# top_schem_rev10_2.net
KiCad netlist of a schematic drawn in Altium Designer
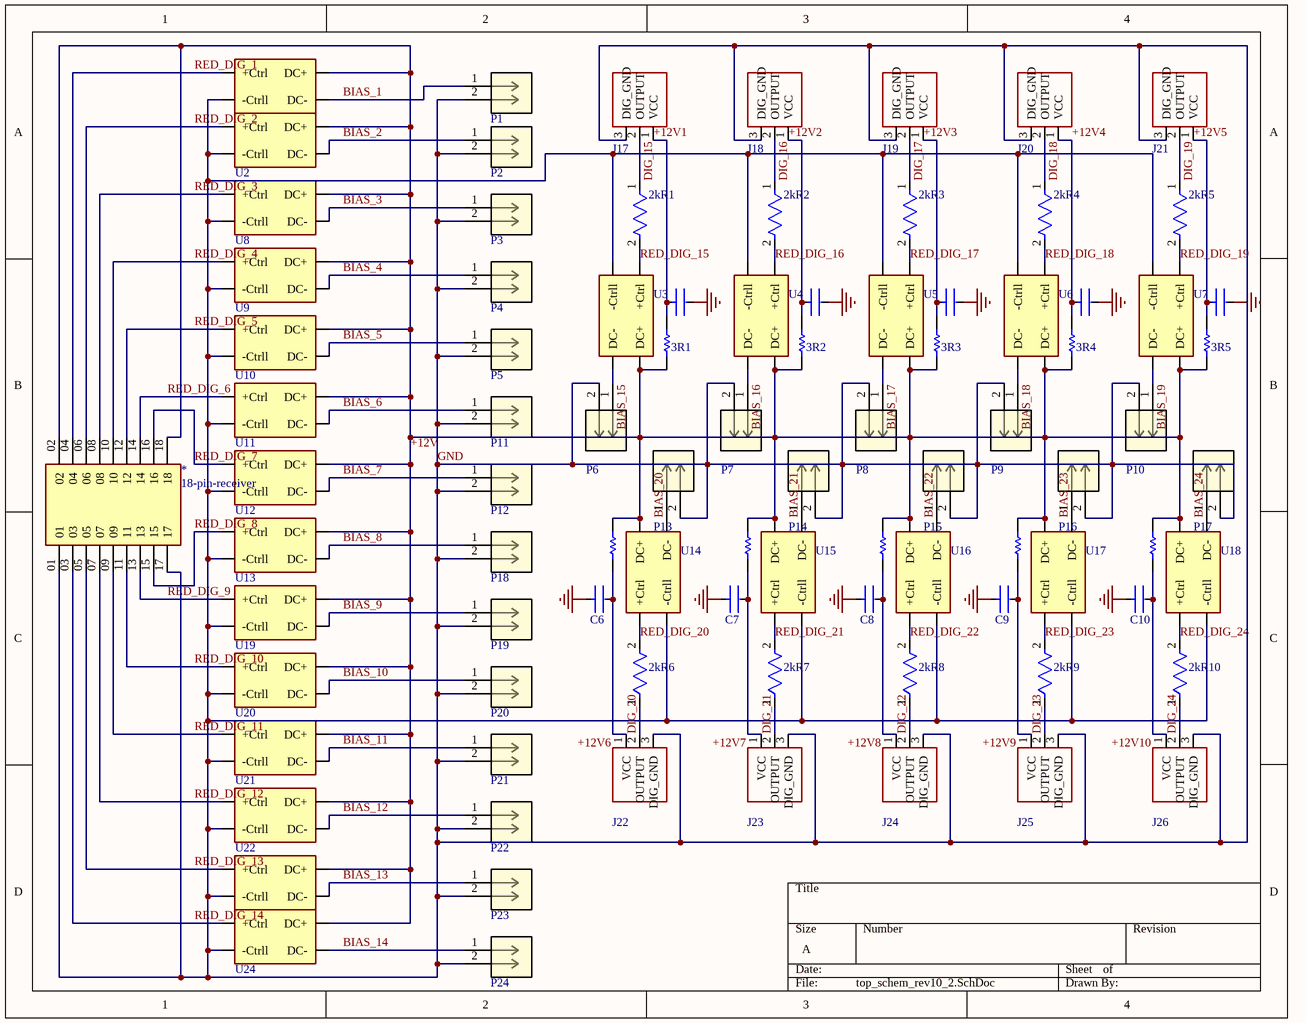
[diagram p0: top_schem_rev10_2.SchDoc]

(export (version "E")
  (design (tool "Eeschema 10.0.6"))
  (components
    (comp (ref "*")
      (value "18-pin-receiver")
      (footprint "18-pin-receiver")
      (libsource (lib "top_schlib") (part "18-pin-receiver"))
    )
    (comp (ref "2kR1")
      (value "CRCW06031K80FKEA")
      (footprint "2kOhm")
      (description "Res Thick Film 0603 1.8K Ohm 1% 1/10W ±100ppm/°C Molded SMD Paper T/R")
      (fields (field (name "MANUFACTURER") "Vishay") (field (name "TOLERANCE") "1%"))
      (libsource (lib "ps_schlib") (part "CRCW06031K80FKEA"))
    )
    (comp (ref "2kR2")
      (value "CRCW06031K80FKEA")
      (footprint "2kOhm")
      (description "Res Thick Film 0603 1.8K Ohm 1% 1/10W ±100ppm/°C Molded SMD Paper T/R")
      (fields (field (name "MANUFACTURER") "Vishay") (field (name "TOLERANCE") "1%"))
      (libsource (lib "ps_schlib") (part "CRCW06031K80FKEA"))
    )
    (comp (ref "2kR3")
      (value "CRCW06031K80FKEA")
      (footprint "2kOhm")
      (description "Res Thick Film 0603 1.8K Ohm 1% 1/10W ±100ppm/°C Molded SMD Paper T/R")
      (fields (field (name "MANUFACTURER") "Vishay") (field (name "TOLERANCE") "1%"))
      (libsource (lib "ps_schlib") (part "CRCW06031K80FKEA"))
    )
    (comp (ref "2kR4")
      (value "CRCW06031K80FKEA")
      (footprint "2kOhm")
      (description "Res Thick Film 0603 1.8K Ohm 1% 1/10W ±100ppm/°C Molded SMD Paper T/R")
      (fields (field (name "MANUFACTURER") "Vishay") (field (name "TOLERANCE") "1%"))
      (libsource (lib "ps_schlib") (part "CRCW06031K80FKEA"))
    )
    (comp (ref "2kR5")
      (value "CRCW06031K80FKEA")
      (footprint "2kOhm")
      (description "Res Thick Film 0603 1.8K Ohm 1% 1/10W ±100ppm/°C Molded SMD Paper T/R")
      (fields (field (name "MANUFACTURER") "Vishay") (field (name "TOLERANCE") "1%"))
      (libsource (lib "ps_schlib") (part "CRCW06031K80FKEA"))
    )
    (comp (ref "2kR6")
      (value "CRCW06031K80FKEA")
      (footprint "2kOhm")
      (description "Res Thick Film 0603 1.8K Ohm 1% 1/10W ±100ppm/°C Molded SMD Paper T/R")
      (fields (field (name "MANUFACTURER") "Vishay") (field (name "TOLERANCE") "1%"))
      (libsource (lib "ps_schlib") (part "CRCW06031K80FKEA"))
    )
    (comp (ref "2kR7")
      (value "CRCW06031K80FKEA")
      (footprint "2kOhm")
      (description "Res Thick Film 0603 1.8K Ohm 1% 1/10W ±100ppm/°C Molded SMD Paper T/R")
      (fields (field (name "MANUFACTURER") "Vishay") (field (name "TOLERANCE") "1%"))
      (libsource (lib "ps_schlib") (part "CRCW06031K80FKEA"))
    )
    (comp (ref "2kR8")
      (value "CRCW06031K80FKEA")
      (footprint "2kOhm")
      (description "Res Thick Film 0603 1.8K Ohm 1% 1/10W ±100ppm/°C Molded SMD Paper T/R")
      (fields (field (name "MANUFACTURER") "Vishay") (field (name "TOLERANCE") "1%"))
      (libsource (lib "ps_schlib") (part "CRCW06031K80FKEA"))
    )
    (comp (ref "2kR9")
      (value "CRCW06031K80FKEA")
      (footprint "2kOhm")
      (description "Res Thick Film 0603 1.8K Ohm 1% 1/10W ±100ppm/°C Molded SMD Paper T/R")
      (fields (field (name "MANUFACTURER") "Vishay") (field (name "TOLERANCE") "1%"))
      (libsource (lib "ps_schlib") (part "CRCW06031K80FKEA"))
    )
    (comp (ref "2kR10")
      (value "CRCW06031K80FKEA")
      (footprint "2kOhm")
      (description "Res Thick Film 0603 1.8K Ohm 1% 1/10W ±100ppm/°C Molded SMD Paper T/R")
      (fields (field (name "MANUFACTURER") "Vishay") (field (name "TOLERANCE") "1%"))
      (libsource (lib "ps_schlib") (part "CRCW06031K80FKEA"))
    )
    (comp (ref "3R1")
      (value "ERJ-2BQJR30X")
      (footprint "03 Ohm")
      (description "RES 0.3 OHM 5% 1/6W 0402")
      (fields (field (name "MANUFACTURER") "Panasonic") (field (name "TOLERANCE") "5%"))
      (libsource (lib "ps_schlib") (part "ERJ-2BQJR30X"))
    )
    (comp (ref "3R2")
      (value "ERJ-2BQJR30X")
      (footprint "03 Ohm")
      (description "RES 0.3 OHM 5% 1/6W 0402")
      (fields (field (name "MANUFACTURER") "Panasonic") (field (name "TOLERANCE") "5%"))
      (libsource (lib "ps_schlib") (part "ERJ-2BQJR30X"))
    )
    (comp (ref "3R3")
      (value "ERJ-2BQJR30X")
      (footprint "03 Ohm")
      (description "RES 0.3 OHM 5% 1/6W 0402")
      (fields (field (name "MANUFACTURER") "Panasonic") (field (name "TOLERANCE") "5%"))
      (libsource (lib "ps_schlib") (part "ERJ-2BQJR30X"))
    )
    (comp (ref "3R4")
      (value "ERJ-2BQJR30X")
      (footprint "03 Ohm")
      (description "RES 0.3 OHM 5% 1/6W 0402")
      (fields (field (name "MANUFACTURER") "Panasonic") (field (name "TOLERANCE") "5%"))
      (libsource (lib "ps_schlib") (part "ERJ-2BQJR30X"))
    )
    (comp (ref "3R5")
      (value "ERJ-2BQJR30X")
      (footprint "03 Ohm")
      (description "RES 0.3 OHM 5% 1/6W 0402")
      (fields (field (name "MANUFACTURER") "Panasonic") (field (name "TOLERANCE") "5%"))
      (libsource (lib "ps_schlib") (part "ERJ-2BQJR30X"))
    )
    (comp (ref "3R6")
      (value "ERJ-2BQJR30X")
      (footprint "03 Ohm")
      (description "RES 0.3 OHM 5% 1/6W 0402")
      (fields (field (name "MANUFACTURER") "Panasonic") (field (name "TOLERANCE") "5%"))
      (libsource (lib "ps_schlib") (part "ERJ-2BQJR30X"))
    )
    (comp (ref "3R7")
      (value "ERJ-2BQJR30X")
      (footprint "03 Ohm")
      (description "RES 0.3 OHM 5% 1/6W 0402")
      (fields (field (name "MANUFACTURER") "Panasonic") (field (name "TOLERANCE") "5%"))
      (libsource (lib "ps_schlib") (part "ERJ-2BQJR30X"))
    )
    (comp (ref "3R8")
      (value "ERJ-2BQJR30X")
      (footprint "03 Ohm")
      (description "RES 0.3 OHM 5% 1/6W 0402")
      (fields (field (name "MANUFACTURER") "Panasonic") (field (name "TOLERANCE") "5%"))
      (libsource (lib "ps_schlib") (part "ERJ-2BQJR30X"))
    )
    (comp (ref "3R9")
      (value "ERJ-2BQJR30X")
      (footprint "03 Ohm")
      (description "RES 0.3 OHM 5% 1/6W 0402")
      (fields (field (name "MANUFACTURER") "Panasonic") (field (name "TOLERANCE") "5%"))
      (libsource (lib "ps_schlib") (part "ERJ-2BQJR30X"))
    )
    (comp (ref "3R10")
      (value "ERJ-2BQJR30X")
      (footprint "03 Ohm")
      (description "RES 0.3 OHM 5% 1/6W 0402")
      (fields (field (name "MANUFACTURER") "Panasonic") (field (name "TOLERANCE") "5%"))
      (libsource (lib "ps_schlib") (part "ERJ-2BQJR30X"))
    )
    (comp (ref "C1")
      (value "C0805C104K5RACTU")
      (footprint "100nF")
      (description "Cap Ceramic 0.1uF 50V X7R 10% SMD 2.0 x 1.2 mm 125 C Paper T/R")
      (fields (field (name "MANUFACTURER") "KEMET") (field (name "TOLERANCE") "10%"))
      (libsource (lib "ps_schlib") (part "C0805C104K5RACTU"))
    )
    (comp (ref "C2")
      (value "C0805C104K5RACTU")
      (footprint "100nF")
      (description "Cap Ceramic 0.1uF 50V X7R 10% SMD 2.0 x 1.2 mm 125 C Paper T/R")
      (fields (field (name "MANUFACTURER") "KEMET") (field (name "TOLERANCE") "10%"))
      (libsource (lib "ps_schlib") (part "C0805C104K5RACTU"))
    )
    (comp (ref "C3")
      (value "C0805C104K5RACTU")
      (footprint "100nF")
      (description "Cap Ceramic 0.1uF 50V X7R 10% SMD 2.0 x 1.2 mm 125 C Paper T/R")
      (fields (field (name "MANUFACTURER") "KEMET") (field (name "TOLERANCE") "10%"))
      (libsource (lib "ps_schlib") (part "C0805C104K5RACTU"))
    )
    (comp (ref "C4")
      (value "C0805C104K5RACTU")
      (footprint "100nF")
      (description "Cap Ceramic 0.1uF 50V X7R 10% SMD 2.0 x 1.2 mm 125 C Paper T/R")
      (fields (field (name "MANUFACTURER") "KEMET") (field (name "TOLERANCE") "10%"))
      (libsource (lib "ps_schlib") (part "C0805C104K5RACTU"))
    )
    (comp (ref "C5")
      (value "C0805C104K5RACTU")
      (footprint "100nF")
      (description "Cap Ceramic 0.1uF 50V X7R 10% SMD 2.0 x 1.2 mm 125 C Paper T/R")
      (fields (field (name "MANUFACTURER") "KEMET") (field (name "TOLERANCE") "10%"))
      (libsource (lib "ps_schlib") (part "C0805C104K5RACTU"))
    )
    (comp (ref "C6")
      (value "C0805C104K5RACTU")
      (footprint "100nF")
      (description "Cap Ceramic 0.1uF 50V X7R 10% SMD 2.0 x 1.2 mm 125 C Paper T/R")
      (fields (field (name "MANUFACTURER") "KEMET") (field (name "TOLERANCE") "10%"))
      (libsource (lib "ps_schlib") (part "C0805C104K5RACTU"))
    )
    (comp (ref "C7")
      (value "C0805C104K5RACTU")
      (footprint "100nF")
      (description "Cap Ceramic 0.1uF 50V X7R 10% SMD 2.0 x 1.2 mm 125 C Paper T/R")
      (fields (field (name "MANUFACTURER") "KEMET") (field (name "TOLERANCE") "10%"))
      (libsource (lib "ps_schlib") (part "C0805C104K5RACTU"))
    )
    (comp (ref "C8")
      (value "C0805C104K5RACTU")
      (footprint "100nF")
      (description "Cap Ceramic 0.1uF 50V X7R 10% SMD 2.0 x 1.2 mm 125 C Paper T/R")
      (fields (field (name "MANUFACTURER") "KEMET") (field (name "TOLERANCE") "10%"))
      (libsource (lib "ps_schlib") (part "C0805C104K5RACTU"))
    )
    (comp (ref "C9")
      (value "C0805C104K5RACTU")
      (footprint "100nF")
      (description "Cap Ceramic 0.1uF 50V X7R 10% SMD 2.0 x 1.2 mm 125 C Paper T/R")
      (fields (field (name "MANUFACTURER") "KEMET") (field (name "TOLERANCE") "10%"))
      (libsource (lib "ps_schlib") (part "C0805C104K5RACTU"))
    )
    (comp (ref "C10")
      (value "C0805C104K5RACTU")
      (footprint "100nF")
      (description "Cap Ceramic 0.1uF 50V X7R 10% SMD 2.0 x 1.2 mm 125 C Paper T/R")
      (fields (field (name "MANUFACTURER") "KEMET") (field (name "TOLERANCE") "10%"))
      (libsource (lib "ps_schlib") (part "C0805C104K5RACTU"))
    )
    (comp (ref "J17")
      (value "IF-D95T")
      (footprint "IF-D95")
      (description "DETECTOR PHOTOLOGIC TTL/CMOS")
      (fields (field (name "MANUFACTURER") "Industrial Fiber Optics"))
      (libsource (lib "ps_schlib") (part "IF-D95T"))
    )
    (comp (ref "J18")
      (value "IF-D95T")
      (footprint "IF-D95")
      (description "DETECTOR PHOTOLOGIC TTL/CMOS")
      (fields (field (name "MANUFACTURER") "Industrial Fiber Optics"))
      (libsource (lib "ps_schlib") (part "IF-D95T"))
    )
    (comp (ref "J19")
      (value "IF-D95T")
      (footprint "IF-D95")
      (description "DETECTOR PHOTOLOGIC TTL/CMOS")
      (fields (field (name "MANUFACTURER") "Industrial Fiber Optics"))
      (libsource (lib "ps_schlib") (part "IF-D95T"))
    )
    (comp (ref "J20")
      (value "IF-D95T")
      (footprint "IF-D95")
      (description "DETECTOR PHOTOLOGIC TTL/CMOS")
      (fields (field (name "MANUFACTURER") "Industrial Fiber Optics"))
      (libsource (lib "ps_schlib") (part "IF-D95T"))
    )
    (comp (ref "J21")
      (value "IF-D95T")
      (footprint "IF-D95")
      (description "DETECTOR PHOTOLOGIC TTL/CMOS")
      (fields (field (name "MANUFACTURER") "Industrial Fiber Optics"))
      (libsource (lib "ps_schlib") (part "IF-D95T"))
    )
    (comp (ref "J22")
      (value "IF-D95T")
      (footprint "IF-D95")
      (description "DETECTOR PHOTOLOGIC TTL/CMOS")
      (fields (field (name "MANUFACTURER") "Industrial Fiber Optics"))
      (libsource (lib "ps_schlib") (part "IF-D95T"))
    )
    (comp (ref "J23")
      (value "IF-D95T")
      (footprint "IF-D95")
      (description "DETECTOR PHOTOLOGIC TTL/CMOS")
      (fields (field (name "MANUFACTURER") "Industrial Fiber Optics"))
      (libsource (lib "ps_schlib") (part "IF-D95T"))
    )
    (comp (ref "J24")
      (value "IF-D95T")
      (footprint "IF-D95")
      (description "DETECTOR PHOTOLOGIC TTL/CMOS")
      (fields (field (name "MANUFACTURER") "Industrial Fiber Optics"))
      (libsource (lib "ps_schlib") (part "IF-D95T"))
    )
    (comp (ref "J25")
      (value "IF-D95T")
      (footprint "IF-D95")
      (description "DETECTOR PHOTOLOGIC TTL/CMOS")
      (fields (field (name "MANUFACTURER") "Industrial Fiber Optics"))
      (libsource (lib "ps_schlib") (part "IF-D95T"))
    )
    (comp (ref "J26")
      (value "IF-D95T")
      (footprint "IF-D95")
      (description "DETECTOR PHOTOLOGIC TTL/CMOS")
      (fields (field (name "MANUFACTURER") "Industrial Fiber Optics"))
      (libsource (lib "ps_schlib") (part "IF-D95T"))
    )
    (comp (ref "P1")
      (value "1054311102")
      (footprint "CONN_1054311102_MOL")
      (fields (field (name "MANUFACTURER") "Molex"))
      (libsource (lib "ps_schlib") (part "1054311102"))
    )
    (comp (ref "P2")
      (value "1054311102")
      (footprint "CONN_1054311102_MOL")
      (fields (field (name "MANUFACTURER") "Molex"))
      (libsource (lib "ps_schlib") (part "1054311102"))
    )
    (comp (ref "P3")
      (value "1054311102")
      (footprint "CONN_1054311102_MOL")
      (fields (field (name "MANUFACTURER") "Molex"))
      (libsource (lib "ps_schlib") (part "1054311102"))
    )
    (comp (ref "P4")
      (value "1054311102")
      (footprint "CONN_1054311102_MOL")
      (fields (field (name "MANUFACTURER") "Molex"))
      (libsource (lib "ps_schlib") (part "1054311102"))
    )
    (comp (ref "P5")
      (value "1054311102")
      (footprint "CONN_1054311102_MOL")
      (fields (field (name "MANUFACTURER") "Molex"))
      (libsource (lib "ps_schlib") (part "1054311102"))
    )
    (comp (ref "P6")
      (value "1054311102")
      (footprint "CONN_1054311102_MOL")
      (fields (field (name "MANUFACTURER") "Molex"))
      (libsource (lib "") (part "1054311102_2"))
    )
    (comp (ref "P7")
      (value "1054311102")
      (footprint "CONN_1054311102_MOL")
      (fields (field (name "MANUFACTURER") "Molex"))
      (libsource (lib "") (part "1054311102_2"))
    )
    (comp (ref "P8")
      (value "1054311102")
      (footprint "CONN_1054311102_MOL")
      (fields (field (name "MANUFACTURER") "Molex"))
      (libsource (lib "") (part "1054311102_2"))
    )
    (comp (ref "P9")
      (value "1054311102")
      (footprint "CONN_1054311102_MOL")
      (fields (field (name "MANUFACTURER") "Molex"))
      (libsource (lib "") (part "1054311102_2"))
    )
    (comp (ref "P10")
      (value "1054311102")
      (footprint "CONN_1054311102_MOL")
      (fields (field (name "MANUFACTURER") "Molex"))
      (libsource (lib "") (part "1054311102_2"))
    )
    (comp (ref "P11")
      (value "1054311102")
      (footprint "CONN_1054311102_MOL")
      (fields (field (name "MANUFACTURER") "Molex"))
      (libsource (lib "ps_schlib") (part "1054311102"))
    )
    (comp (ref "P12")
      (value "1054311102")
      (footprint "CONN_1054311102_MOL")
      (fields (field (name "MANUFACTURER") "Molex"))
      (libsource (lib "ps_schlib") (part "1054311102"))
    )
    (comp (ref "P13")
      (value "1054311102")
      (footprint "CONN_1054311102_MOL")
      (fields (field (name "MANUFACTURER") "Molex"))
      (libsource (lib "") (part "1054311102_1"))
    )
    (comp (ref "P14")
      (value "1054311102")
      (footprint "CONN_1054311102_MOL")
      (fields (field (name "MANUFACTURER") "Molex"))
      (libsource (lib "") (part "1054311102_1"))
    )
    (comp (ref "P15")
      (value "1054311102")
      (footprint "CONN_1054311102_MOL")
      (fields (field (name "MANUFACTURER") "Molex"))
      (libsource (lib "") (part "1054311102_1"))
    )
    (comp (ref "P16")
      (value "1054311102")
      (footprint "CONN_1054311102_MOL")
      (fields (field (name "MANUFACTURER") "Molex"))
      (libsource (lib "") (part "1054311102_1"))
    )
    (comp (ref "P17")
      (value "1054311102")
      (footprint "CONN_1054311102_MOL")
      (fields (field (name "MANUFACTURER") "Molex"))
      (libsource (lib "") (part "1054311102_1"))
    )
    (comp (ref "P18")
      (value "1054311102")
      (footprint "CONN_1054311102_MOL")
      (fields (field (name "MANUFACTURER") "Molex"))
      (libsource (lib "ps_schlib") (part "1054311102"))
    )
    (comp (ref "P19")
      (value "1054311102")
      (footprint "CONN_1054311102_MOL")
      (fields (field (name "MANUFACTURER") "Molex"))
      (libsource (lib "ps_schlib") (part "1054311102"))
    )
    (comp (ref "P20")
      (value "1054311102")
      (footprint "CONN_1054311102_MOL")
      (fields (field (name "MANUFACTURER") "Molex"))
      (libsource (lib "ps_schlib") (part "1054311102"))
    )
    (comp (ref "P21")
      (value "1054311102")
      (footprint "CONN_1054311102_MOL")
      (fields (field (name "MANUFACTURER") "Molex"))
      (libsource (lib "ps_schlib") (part "1054311102"))
    )
    (comp (ref "P22")
      (value "1054311102")
      (footprint "CONN_1054311102_MOL")
      (fields (field (name "MANUFACTURER") "Molex"))
      (libsource (lib "ps_schlib") (part "1054311102"))
    )
    (comp (ref "P23")
      (value "1054311102")
      (footprint "CONN_1054311102_MOL")
      (fields (field (name "MANUFACTURER") "Molex"))
      (libsource (lib "ps_schlib") (part "1054311102"))
    )
    (comp (ref "P24")
      (value "1054311102")
      (footprint "CONN_1054311102_MOL")
      (fields (field (name "MANUFACTURER") "Molex"))
      (libsource (lib "ps_schlib") (part "1054311102"))
    )
    (comp (ref "U1")
      (value "Solid state relay")
      (footprint "CPC1002N")
      (libsource (lib "ps_schlib") (part "CPC1002N"))
    )
    (comp (ref "U2")
      (value "Solid state relay")
      (footprint "CPC1002N")
      (libsource (lib "ps_schlib") (part "CPC1002N"))
    )
    (comp (ref "U3")
      (value "Solid state relay")
      (footprint "CPC1002N")
      (libsource (lib "") (part "CPC1002N_2"))
    )
    (comp (ref "U4")
      (value "Solid state relay")
      (footprint "CPC1002N")
      (libsource (lib "") (part "CPC1002N_2"))
    )
    (comp (ref "U5")
      (value "Solid state relay")
      (footprint "CPC1002N")
      (libsource (lib "") (part "CPC1002N_2"))
    )
    (comp (ref "U6")
      (value "Solid state relay")
      (footprint "CPC1002N")
      (libsource (lib "") (part "CPC1002N_2"))
    )
    (comp (ref "U7")
      (value "Solid state relay")
      (footprint "CPC1002N")
      (libsource (lib "") (part "CPC1002N_2"))
    )
    (comp (ref "U8")
      (value "Solid state relay")
      (footprint "CPC1002N")
      (libsource (lib "ps_schlib") (part "CPC1002N"))
    )
    (comp (ref "U9")
      (value "Solid state relay")
      (footprint "CPC1002N")
      (libsource (lib "ps_schlib") (part "CPC1002N"))
    )
    (comp (ref "U10")
      (value "Solid state relay")
      (footprint "CPC1002N")
      (libsource (lib "ps_schlib") (part "CPC1002N"))
    )
    (comp (ref "U11")
      (value "Solid state relay")
      (footprint "CPC1002N")
      (libsource (lib "ps_schlib") (part "CPC1002N"))
    )
    (comp (ref "U12")
      (value "Solid state relay")
      (footprint "CPC1002N")
      (libsource (lib "ps_schlib") (part "CPC1002N"))
    )
    (comp (ref "U13")
      (value "Solid state relay")
      (footprint "CPC1002N")
      (libsource (lib "ps_schlib") (part "CPC1002N"))
    )
    (comp (ref "U14")
      (value "Solid state relay")
      (footprint "CPC1002N")
      (libsource (lib "") (part "CPC1002N_1"))
    )
    (comp (ref "U15")
      (value "Solid state relay")
      (footprint "CPC1002N")
      (libsource (lib "") (part "CPC1002N_1"))
    )
    (comp (ref "U16")
      (value "Solid state relay")
      (footprint "CPC1002N")
      (libsource (lib "") (part "CPC1002N_1"))
    )
    (comp (ref "U17")
      (value "Solid state relay")
      (footprint "CPC1002N")
      (libsource (lib "") (part "CPC1002N_1"))
    )
    (comp (ref "U18")
      (value "Solid state relay")
      (footprint "CPC1002N")
      (libsource (lib "") (part "CPC1002N_1"))
    )
    (comp (ref "U19")
      (value "Solid state relay")
      (footprint "CPC1002N")
      (libsource (lib "ps_schlib") (part "CPC1002N"))
    )
    (comp (ref "U20")
      (value "Solid state relay")
      (footprint "CPC1002N")
      (libsource (lib "ps_schlib") (part "CPC1002N"))
    )
    (comp (ref "U21")
      (value "Solid state relay")
      (footprint "CPC1002N")
      (libsource (lib "ps_schlib") (part "CPC1002N"))
    )
    (comp (ref "U22")
      (value "Solid state relay")
      (footprint "CPC1002N")
      (libsource (lib "ps_schlib") (part "CPC1002N"))
    )
    (comp (ref "U23")
      (value "Solid state relay")
      (footprint "CPC1002N")
      (libsource (lib "ps_schlib") (part "CPC1002N"))
    )
    (comp (ref "U24")
      (value "Solid state relay")
      (footprint "CPC1002N")
      (libsource (lib "ps_schlib") (part "CPC1002N"))
    )
  )
  (nets
    (net (code "1") (name "/+12V") (class "Default")
      (node (ref "*") (pin "02") (pinfunction "02_02") (pintype "passive"))
      (node (ref "*") (pin "18") (pinfunction "18_18") (pintype "passive"))
      (node (ref "3R1") (pin "1") (pinfunction "1_1") (pintype "passive"))
      (node (ref "3R10") (pin "2") (pinfunction "2_2") (pintype "passive"))
      (node (ref "3R2") (pin "1") (pinfunction "1_1") (pintype "passive"))
      (node (ref "3R3") (pin "1") (pinfunction "1_1") (pintype "passive"))
      (node (ref "3R4") (pin "1") (pinfunction "1_1") (pintype "passive"))
      (node (ref "3R5") (pin "1") (pinfunction "1_1") (pintype "passive"))
      (node (ref "3R6") (pin "2") (pinfunction "2_2") (pintype "passive"))
      (node (ref "3R7") (pin "2") (pinfunction "2_2") (pintype "passive"))
      (node (ref "3R8") (pin "2") (pinfunction "2_2") (pintype "passive"))
      (node (ref "3R9") (pin "2") (pinfunction "2_2") (pintype "passive"))
      (node (ref "U1") (pin "4") (pinfunction "DC+_4") (pintype "passive"))
      (node (ref "U10") (pin "4") (pinfunction "DC+_4") (pintype "passive"))
      (node (ref "U11") (pin "4") (pinfunction "DC+_4") (pintype "passive"))
      (node (ref "U12") (pin "4") (pinfunction "DC+_4") (pintype "passive"))
      (node (ref "U13") (pin "4") (pinfunction "DC+_4") (pintype "passive"))
      (node (ref "U14") (pin "4") (pinfunction "DC+_4") (pintype "passive"))
      (node (ref "U15") (pin "4") (pinfunction "DC+_4") (pintype "passive"))
      (node (ref "U16") (pin "4") (pinfunction "DC+_4") (pintype "passive"))
      (node (ref "U17") (pin "4") (pinfunction "DC+_4") (pintype "passive"))
      (node (ref "U18") (pin "4") (pinfunction "DC+_4") (pintype "passive"))
      (node (ref "U19") (pin "4") (pinfunction "DC+_4") (pintype "passive"))
      (node (ref "U2") (pin "4") (pinfunction "DC+_4") (pintype "passive"))
      (node (ref "U20") (pin "4") (pinfunction "DC+_4") (pintype "passive"))
      (node (ref "U21") (pin "4") (pinfunction "DC+_4") (pintype "passive"))
      (node (ref "U22") (pin "4") (pinfunction "DC+_4") (pintype "passive"))
      (node (ref "U23") (pin "4") (pinfunction "DC+_4") (pintype "passive"))
      (node (ref "U24") (pin "4") (pinfunction "DC+_4") (pintype "passive"))
      (node (ref "U3") (pin "4") (pinfunction "DC+_4") (pintype "passive"))
      (node (ref "U4") (pin "4") (pinfunction "DC+_4") (pintype "passive"))
      (node (ref "U5") (pin "4") (pinfunction "DC+_4") (pintype "passive"))
      (node (ref "U6") (pin "4") (pinfunction "DC+_4") (pintype "passive"))
      (node (ref "U7") (pin "4") (pinfunction "DC+_4") (pintype "passive"))
      (node (ref "U8") (pin "4") (pinfunction "DC+_4") (pintype "passive"))
      (node (ref "U9") (pin "4") (pinfunction "DC+_4") (pintype "passive"))
    )
    (net (code "2") (name "/+12V1") (class "Default")
      (node (ref "3R1") (pin "2") (pinfunction "2_2") (pintype "passive"))
      (node (ref "C1") (pin "1") (pinfunction "1_1") (pintype "passive"))
      (node (ref "J17") (pin "1") (pinfunction "VCC_1") (pintype "passive"))
    )
    (net (code "3") (name "/+12V2") (class "Default")
      (node (ref "3R2") (pin "2") (pinfunction "2_2") (pintype "passive"))
      (node (ref "C2") (pin "1") (pinfunction "1_1") (pintype "passive"))
      (node (ref "J18") (pin "1") (pinfunction "VCC_1") (pintype "passive"))
    )
    (net (code "4") (name "/+12V3") (class "Default")
      (node (ref "3R3") (pin "2") (pinfunction "2_2") (pintype "passive"))
      (node (ref "C3") (pin "1") (pinfunction "1_1") (pintype "passive"))
      (node (ref "J19") (pin "1") (pinfunction "VCC_1") (pintype "passive"))
    )
    (net (code "5") (name "/+12V4") (class "Default")
      (node (ref "3R4") (pin "2") (pinfunction "2_2") (pintype "passive"))
      (node (ref "C4") (pin "1") (pinfunction "1_1") (pintype "passive"))
      (node (ref "J20") (pin "1") (pinfunction "VCC_1") (pintype "passive"))
    )
    (net (code "6") (name "/+12V5") (class "Default")
      (node (ref "3R5") (pin "2") (pinfunction "2_2") (pintype "passive"))
      (node (ref "C5") (pin "1") (pinfunction "1_1") (pintype "passive"))
      (node (ref "J21") (pin "1") (pinfunction "VCC_1") (pintype "passive"))
    )
    (net (code "7") (name "/+12V6") (class "Default")
      (node (ref "3R6") (pin "1") (pinfunction "1_1") (pintype "passive"))
      (node (ref "C6") (pin "2") (pinfunction "2_2") (pintype "passive"))
      (node (ref "J22") (pin "1") (pinfunction "VCC_1") (pintype "passive"))
    )
    (net (code "8") (name "/+12V7") (class "Default")
      (node (ref "3R7") (pin "1") (pinfunction "1_1") (pintype "passive"))
      (node (ref "C7") (pin "2") (pinfunction "2_2") (pintype "passive"))
      (node (ref "J23") (pin "1") (pinfunction "VCC_1") (pintype "passive"))
    )
    (net (code "9") (name "/+12V8") (class "Default")
      (node (ref "3R8") (pin "1") (pinfunction "1_1") (pintype "passive"))
      (node (ref "C8") (pin "2") (pinfunction "2_2") (pintype "passive"))
      (node (ref "J24") (pin "1") (pinfunction "VCC_1") (pintype "passive"))
    )
    (net (code "10") (name "/+12V9") (class "Default")
      (node (ref "3R9") (pin "1") (pinfunction "1_1") (pintype "passive"))
      (node (ref "C9") (pin "2") (pinfunction "2_2") (pintype "passive"))
      (node (ref "J25") (pin "1") (pinfunction "VCC_1") (pintype "passive"))
    )
    (net (code "11") (name "/+12V10") (class "Default")
      (node (ref "3R10") (pin "1") (pinfunction "1_1") (pintype "passive"))
      (node (ref "C10") (pin "2") (pinfunction "2_2") (pintype "passive"))
      (node (ref "J26") (pin "1") (pinfunction "VCC_1") (pintype "passive"))
    )
    (net (code "12") (name "/BIAS_1") (class "Default")
      (node (ref "P1") (pin "1") (pinfunction "1_1") (pintype "passive"))
      (node (ref "U1") (pin "3") (pinfunction "DC-_3") (pintype "passive"))
    )
    (net (code "13") (name "/BIAS_2") (class "Default")
      (node (ref "P2") (pin "1") (pinfunction "1_1") (pintype "passive"))
      (node (ref "U2") (pin "3") (pinfunction "DC-_3") (pintype "passive"))
    )
    (net (code "14") (name "/BIAS_3") (class "Default")
      (node (ref "P3") (pin "1") (pinfunction "1_1") (pintype "passive"))
      (node (ref "U8") (pin "3") (pinfunction "DC-_3") (pintype "passive"))
    )
    (net (code "15") (name "/BIAS_4") (class "Default")
      (node (ref "P4") (pin "1") (pinfunction "1_1") (pintype "passive"))
      (node (ref "U9") (pin "3") (pinfunction "DC-_3") (pintype "passive"))
    )
    (net (code "16") (name "/BIAS_5") (class "Default")
      (node (ref "P5") (pin "1") (pinfunction "1_1") (pintype "passive"))
      (node (ref "U10") (pin "3") (pinfunction "DC-_3") (pintype "passive"))
    )
    (net (code "17") (name "/BIAS_6") (class "Default")
      (node (ref "P11") (pin "1") (pinfunction "1_1") (pintype "passive"))
      (node (ref "U11") (pin "3") (pinfunction "DC-_3") (pintype "passive"))
    )
    (net (code "18") (name "/BIAS_7") (class "Default")
      (node (ref "P12") (pin "1") (pinfunction "1_1") (pintype "passive"))
      (node (ref "U12") (pin "3") (pinfunction "DC-_3") (pintype "passive"))
    )
    (net (code "19") (name "/BIAS_8") (class "Default")
      (node (ref "P18") (pin "1") (pinfunction "1_1") (pintype "passive"))
      (node (ref "U13") (pin "3") (pinfunction "DC-_3") (pintype "passive"))
    )
    (net (code "20") (name "/BIAS_9") (class "Default")
      (node (ref "P19") (pin "1") (pinfunction "1_1") (pintype "passive"))
      (node (ref "U19") (pin "3") (pinfunction "DC-_3") (pintype "passive"))
    )
    (net (code "21") (name "/BIAS_10") (class "Default")
      (node (ref "P20") (pin "1") (pinfunction "1_1") (pintype "passive"))
      (node (ref "U20") (pin "3") (pinfunction "DC-_3") (pintype "passive"))
    )
    (net (code "22") (name "/BIAS_11") (class "Default")
      (node (ref "P21") (pin "1") (pinfunction "1_1") (pintype "passive"))
      (node (ref "U21") (pin "3") (pinfunction "DC-_3") (pintype "passive"))
    )
    (net (code "23") (name "/BIAS_12") (class "Default")
      (node (ref "P22") (pin "1") (pinfunction "1_1") (pintype "passive"))
      (node (ref "U22") (pin "3") (pinfunction "DC-_3") (pintype "passive"))
    )
    (net (code "24") (name "/BIAS_13") (class "Default")
      (node (ref "P23") (pin "1") (pinfunction "1_1") (pintype "passive"))
      (node (ref "U23") (pin "3") (pinfunction "DC-_3") (pintype "passive"))
    )
    (net (code "25") (name "/BIAS_14") (class "Default")
      (node (ref "P24") (pin "1") (pinfunction "1_1") (pintype "passive"))
      (node (ref "U24") (pin "3") (pinfunction "DC-_3") (pintype "passive"))
    )
    (net (code "26") (name "/BIAS_15") (class "Default")
      (node (ref "P6") (pin "1") (pinfunction "1_1") (pintype "passive"))
      (node (ref "U3") (pin "3") (pinfunction "DC-_3") (pintype "passive"))
    )
    (net (code "27") (name "/BIAS_16") (class "Default")
      (node (ref "P7") (pin "1") (pinfunction "1_1") (pintype "passive"))
      (node (ref "U4") (pin "3") (pinfunction "DC-_3") (pintype "passive"))
    )
    (net (code "28") (name "/BIAS_17") (class "Default")
      (node (ref "P8") (pin "1") (pinfunction "1_1") (pintype "passive"))
      (node (ref "U5") (pin "3") (pinfunction "DC-_3") (pintype "passive"))
    )
    (net (code "29") (name "/BIAS_18") (class "Default")
      (node (ref "P9") (pin "1") (pinfunction "1_1") (pintype "passive"))
      (node (ref "U6") (pin "3") (pinfunction "DC-_3") (pintype "passive"))
    )
    (net (code "30") (name "/BIAS_19") (class "Default")
      (node (ref "P10") (pin "1") (pinfunction "1_1") (pintype "passive"))
      (node (ref "U7") (pin "3") (pinfunction "DC-_3") (pintype "passive"))
    )
    (net (code "31") (name "/BIAS_20") (class "Default")
      (node (ref "P13") (pin "1") (pinfunction "1_1") (pintype "passive"))
      (node (ref "U14") (pin "3") (pinfunction "DC-_3") (pintype "passive"))
    )
    (net (code "32") (name "/BIAS_21") (class "Default")
      (node (ref "P14") (pin "1") (pinfunction "1_1") (pintype "passive"))
      (node (ref "U15") (pin "3") (pinfunction "DC-_3") (pintype "passive"))
    )
    (net (code "33") (name "/BIAS_22") (class "Default")
      (node (ref "P15") (pin "1") (pinfunction "1_1") (pintype "passive"))
      (node (ref "U16") (pin "3") (pinfunction "DC-_3") (pintype "passive"))
    )
    (net (code "34") (name "/BIAS_23") (class "Default")
      (node (ref "P16") (pin "1") (pinfunction "1_1") (pintype "passive"))
      (node (ref "U17") (pin "3") (pinfunction "DC-_3") (pintype "passive"))
    )
    (net (code "35") (name "/BIAS_24") (class "Default")
      (node (ref "P17") (pin "1") (pinfunction "1_1") (pintype "passive"))
      (node (ref "U18") (pin "3") (pinfunction "DC-_3") (pintype "passive"))
    )
    (net (code "36") (name "/DIG_15") (class "Default")
      (node (ref "2kR1") (pin "1") (pinfunction "1_1") (pintype "passive"))
      (node (ref "J17") (pin "2") (pinfunction "OUTPUT_2") (pintype "passive"))
    )
    (net (code "37") (name "/DIG_16") (class "Default")
      (node (ref "2kR2") (pin "1") (pinfunction "1_1") (pintype "passive"))
      (node (ref "J18") (pin "2") (pinfunction "OUTPUT_2") (pintype "passive"))
    )
    (net (code "38") (name "/DIG_17") (class "Default")
      (node (ref "2kR3") (pin "1") (pinfunction "1_1") (pintype "passive"))
      (node (ref "J19") (pin "2") (pinfunction "OUTPUT_2") (pintype "passive"))
    )
    (net (code "39") (name "/DIG_18") (class "Default")
      (node (ref "2kR4") (pin "1") (pinfunction "1_1") (pintype "passive"))
      (node (ref "J20") (pin "2") (pinfunction "OUTPUT_2") (pintype "passive"))
    )
    (net (code "40") (name "/DIG_19") (class "Default")
      (node (ref "2kR5") (pin "1") (pinfunction "1_1") (pintype "passive"))
      (node (ref "J21") (pin "2") (pinfunction "OUTPUT_2") (pintype "passive"))
    )
    (net (code "41") (name "/DIG_20") (class "Default")
      (node (ref "2kR6") (pin "1") (pinfunction "1_1") (pintype "passive"))
      (node (ref "J22") (pin "2") (pinfunction "OUTPUT_2") (pintype "passive"))
    )
    (net (code "42") (name "/DIG_21") (class "Default")
      (node (ref "2kR7") (pin "1") (pinfunction "1_1") (pintype "passive"))
      (node (ref "J23") (pin "2") (pinfunction "OUTPUT_2") (pintype "passive"))
    )
    (net (code "43") (name "/DIG_22") (class "Default")
      (node (ref "2kR8") (pin "1") (pinfunction "1_1") (pintype "passive"))
      (node (ref "J24") (pin "2") (pinfunction "OUTPUT_2") (pintype "passive"))
    )
    (net (code "44") (name "/DIG_23") (class "Default")
      (node (ref "2kR9") (pin "1") (pinfunction "1_1") (pintype "passive"))
      (node (ref "J25") (pin "2") (pinfunction "OUTPUT_2") (pintype "passive"))
    )
    (net (code "45") (name "/DIG_24") (class "Default")
      (node (ref "2kR10") (pin "1") (pinfunction "1_1") (pintype "passive"))
      (node (ref "J26") (pin "2") (pinfunction "OUTPUT_2") (pintype "passive"))
    )
    (net (code "46") (name "/RED_DIG_1") (class "Default")
      (node (ref "*") (pin "04") (pinfunction "04_04") (pintype "passive"))
      (node (ref "U1") (pin "1") (pinfunction "+Ctrl_1") (pintype "passive"))
    )
    (net (code "47") (name "/RED_DIG_2") (class "Default")
      (node (ref "*") (pin "06") (pinfunction "06_06") (pintype "passive"))
      (node (ref "U2") (pin "1") (pinfunction "+Ctrl_1") (pintype "passive"))
    )
    (net (code "48") (name "/RED_DIG_3") (class "Default")
      (node (ref "*") (pin "08") (pinfunction "08_08") (pintype "passive"))
      (node (ref "U8") (pin "1") (pinfunction "+Ctrl_1") (pintype "passive"))
    )
    (net (code "49") (name "/RED_DIG_4") (class "Default")
      (node (ref "*") (pin "10") (pinfunction "10_10") (pintype "passive"))
      (node (ref "U9") (pin "1") (pinfunction "+Ctrl_1") (pintype "passive"))
    )
    (net (code "50") (name "/RED_DIG_5") (class "Default")
      (node (ref "*") (pin "12") (pinfunction "12_12") (pintype "passive"))
      (node (ref "U10") (pin "1") (pinfunction "+Ctrl_1") (pintype "passive"))
    )
    (net (code "51") (name "/RED_DIG_6") (class "Default")
      (node (ref "*") (pin "14") (pinfunction "14_14") (pintype "passive"))
      (node (ref "U11") (pin "1") (pinfunction "+Ctrl_1") (pintype "passive"))
    )
    (net (code "52") (name "/RED_DIG_7") (class "Default")
      (node (ref "*") (pin "16") (pinfunction "16_16") (pintype "passive"))
      (node (ref "U12") (pin "1") (pinfunction "+Ctrl_1") (pintype "passive"))
    )
    (net (code "53") (name "/RED_DIG_8") (class "Default")
      (node (ref "*") (pin "15") (pinfunction "15_15") (pintype "passive"))
      (node (ref "U13") (pin "1") (pinfunction "+Ctrl_1") (pintype "passive"))
    )
    (net (code "54") (name "/RED_DIG_9") (class "Default")
      (node (ref "*") (pin "13") (pinfunction "13_13") (pintype "passive"))
      (node (ref "U19") (pin "1") (pinfunction "+Ctrl_1") (pintype "passive"))
    )
    (net (code "55") (name "/RED_DIG_10") (class "Default")
      (node (ref "*") (pin "11") (pinfunction "11_11") (pintype "passive"))
      (node (ref "U20") (pin "1") (pinfunction "+Ctrl_1") (pintype "passive"))
    )
    (net (code "56") (name "/RED_DIG_11") (class "Default")
      (node (ref "*") (pin "09") (pinfunction "09_09") (pintype "passive"))
      (node (ref "U21") (pin "1") (pinfunction "+Ctrl_1") (pintype "passive"))
    )
    (net (code "57") (name "/RED_DIG_12") (class "Default")
      (node (ref "*") (pin "07") (pinfunction "07_07") (pintype "passive"))
      (node (ref "U22") (pin "1") (pinfunction "+Ctrl_1") (pintype "passive"))
    )
    (net (code "58") (name "/RED_DIG_13") (class "Default")
      (node (ref "*") (pin "05") (pinfunction "05_05") (pintype "passive"))
      (node (ref "U23") (pin "1") (pinfunction "+Ctrl_1") (pintype "passive"))
    )
    (net (code "59") (name "/RED_DIG_14") (class "Default")
      (node (ref "*") (pin "03") (pinfunction "03_03") (pintype "passive"))
      (node (ref "U24") (pin "1") (pinfunction "+Ctrl_1") (pintype "passive"))
    )
    (net (code "60") (name "/RED_DIG_15") (class "Default")
      (node (ref "2kR1") (pin "2") (pinfunction "2_2") (pintype "passive"))
      (node (ref "U3") (pin "1") (pinfunction "+Ctrl_1") (pintype "passive"))
    )
    (net (code "61") (name "/RED_DIG_16") (class "Default")
      (node (ref "2kR2") (pin "2") (pinfunction "2_2") (pintype "passive"))
      (node (ref "U4") (pin "1") (pinfunction "+Ctrl_1") (pintype "passive"))
    )
    (net (code "62") (name "/RED_DIG_17") (class "Default")
      (node (ref "2kR3") (pin "2") (pinfunction "2_2") (pintype "passive"))
      (node (ref "U5") (pin "1") (pinfunction "+Ctrl_1") (pintype "passive"))
    )
    (net (code "63") (name "/RED_DIG_18") (class "Default")
      (node (ref "2kR4") (pin "2") (pinfunction "2_2") (pintype "passive"))
      (node (ref "U6") (pin "1") (pinfunction "+Ctrl_1") (pintype "passive"))
    )
    (net (code "64") (name "/RED_DIG_19") (class "Default")
      (node (ref "2kR5") (pin "2") (pinfunction "2_2") (pintype "passive"))
      (node (ref "U7") (pin "1") (pinfunction "+Ctrl_1") (pintype "passive"))
    )
    (net (code "65") (name "/RED_DIG_20") (class "Default")
      (node (ref "2kR6") (pin "2") (pinfunction "2_2") (pintype "passive"))
      (node (ref "U14") (pin "1") (pinfunction "+Ctrl_1") (pintype "passive"))
    )
    (net (code "66") (name "/RED_DIG_21") (class "Default")
      (node (ref "2kR7") (pin "2") (pinfunction "2_2") (pintype "passive"))
      (node (ref "U15") (pin "1") (pinfunction "+Ctrl_1") (pintype "passive"))
    )
    (net (code "67") (name "/RED_DIG_22") (class "Default")
      (node (ref "2kR8") (pin "2") (pinfunction "2_2") (pintype "passive"))
      (node (ref "U16") (pin "1") (pinfunction "+Ctrl_1") (pintype "passive"))
    )
    (net (code "68") (name "/RED_DIG_23") (class "Default")
      (node (ref "2kR9") (pin "2") (pinfunction "2_2") (pintype "passive"))
      (node (ref "U17") (pin "1") (pinfunction "+Ctrl_1") (pintype "passive"))
    )
    (net (code "69") (name "/RED_DIG_24") (class "Default")
      (node (ref "2kR10") (pin "2") (pinfunction "2_2") (pintype "passive"))
      (node (ref "U18") (pin "1") (pinfunction "+Ctrl_1") (pintype "passive"))
    )
    (net (code "70") (name "GND") (class "Default")
      (node (ref "*") (pin "01") (pinfunction "01_01") (pintype "passive"))
      (node (ref "*") (pin "17") (pinfunction "17_17") (pintype "passive"))
      (node (ref "C1") (pin "2") (pinfunction "2_2") (pintype "passive"))
      (node (ref "C10") (pin "1") (pinfunction "1_1") (pintype "passive"))
      (node (ref "C2") (pin "2") (pinfunction "2_2") (pintype "passive"))
      (node (ref "C3") (pin "2") (pinfunction "2_2") (pintype "passive"))
      (node (ref "C4") (pin "2") (pinfunction "2_2") (pintype "passive"))
      (node (ref "C5") (pin "2") (pinfunction "2_2") (pintype "passive"))
      (node (ref "C6") (pin "1") (pinfunction "1_1") (pintype "passive"))
      (node (ref "C7") (pin "1") (pinfunction "1_1") (pintype "passive"))
      (node (ref "C8") (pin "1") (pinfunction "1_1") (pintype "passive"))
      (node (ref "C9") (pin "1") (pinfunction "1_1") (pintype "passive"))
      (node (ref "J17") (pin "3") (pinfunction "DIG_GND_3") (pintype "passive"))
      (node (ref "J18") (pin "3") (pinfunction "DIG_GND_3") (pintype "passive"))
      (node (ref "J19") (pin "3") (pinfunction "DIG_GND_3") (pintype "passive"))
      (node (ref "J20") (pin "3") (pinfunction "DIG_GND_3") (pintype "passive"))
      (node (ref "J21") (pin "3") (pinfunction "DIG_GND_3") (pintype "passive"))
      (node (ref "J22") (pin "3") (pinfunction "DIG_GND_3") (pintype "passive"))
      (node (ref "J23") (pin "3") (pinfunction "DIG_GND_3") (pintype "passive"))
      (node (ref "J24") (pin "3") (pinfunction "DIG_GND_3") (pintype "passive"))
      (node (ref "J25") (pin "3") (pinfunction "DIG_GND_3") (pintype "passive"))
      (node (ref "J26") (pin "3") (pinfunction "DIG_GND_3") (pintype "passive"))
      (node (ref "P1") (pin "2") (pinfunction "2_2") (pintype "passive"))
      (node (ref "P10") (pin "2") (pinfunction "2_2") (pintype "passive"))
      (node (ref "P11") (pin "2") (pinfunction "2_2") (pintype "passive"))
      (node (ref "P12") (pin "2") (pinfunction "2_2") (pintype "passive"))
      (node (ref "P13") (pin "2") (pinfunction "2_2") (pintype "passive"))
      (node (ref "P14") (pin "2") (pinfunction "2_2") (pintype "passive"))
      (node (ref "P15") (pin "2") (pinfunction "2_2") (pintype "passive"))
      (node (ref "P16") (pin "2") (pinfunction "2_2") (pintype "passive"))
      (node (ref "P17") (pin "2") (pinfunction "2_2") (pintype "passive"))
      (node (ref "P18") (pin "2") (pinfunction "2_2") (pintype "passive"))
      (node (ref "P19") (pin "2") (pinfunction "2_2") (pintype "passive"))
      (node (ref "P2") (pin "2") (pinfunction "2_2") (pintype "passive"))
      (node (ref "P20") (pin "2") (pinfunction "2_2") (pintype "passive"))
      (node (ref "P21") (pin "2") (pinfunction "2_2") (pintype "passive"))
      (node (ref "P22") (pin "2") (pinfunction "2_2") (pintype "passive"))
      (node (ref "P23") (pin "2") (pinfunction "2_2") (pintype "passive"))
      (node (ref "P24") (pin "2") (pinfunction "2_2") (pintype "passive"))
      (node (ref "P3") (pin "2") (pinfunction "2_2") (pintype "passive"))
      (node (ref "P4") (pin "2") (pinfunction "2_2") (pintype "passive"))
      (node (ref "P5") (pin "2") (pinfunction "2_2") (pintype "passive"))
      (node (ref "P6") (pin "2") (pinfunction "2_2") (pintype "passive"))
      (node (ref "P7") (pin "2") (pinfunction "2_2") (pintype "passive"))
      (node (ref "P8") (pin "2") (pinfunction "2_2") (pintype "passive"))
      (node (ref "P9") (pin "2") (pinfunction "2_2") (pintype "passive"))
      (node (ref "U1") (pin "2") (pinfunction "-Ctrll_2") (pintype "passive"))
      (node (ref "U10") (pin "2") (pinfunction "-Ctrll_2") (pintype "passive"))
      (node (ref "U11") (pin "2") (pinfunction "-Ctrll_2") (pintype "passive"))
      (node (ref "U12") (pin "2") (pinfunction "-Ctrll_2") (pintype "passive"))
      (node (ref "U13") (pin "2") (pinfunction "-Ctrll_2") (pintype "passive"))
      (node (ref "U14") (pin "2") (pinfunction "-Ctrll_2") (pintype "passive"))
      (node (ref "U15") (pin "2") (pinfunction "-Ctrll_2") (pintype "passive"))
      (node (ref "U16") (pin "2") (pinfunction "-Ctrll_2") (pintype "passive"))
      (node (ref "U17") (pin "2") (pinfunction "-Ctrll_2") (pintype "passive"))
      (node (ref "U18") (pin "2") (pinfunction "-Ctrll_2") (pintype "passive"))
      (node (ref "U19") (pin "2") (pinfunction "-Ctrll_2") (pintype "passive"))
      (node (ref "U2") (pin "2") (pinfunction "-Ctrll_2") (pintype "passive"))
      (node (ref "U20") (pin "2") (pinfunction "-Ctrll_2") (pintype "passive"))
      (node (ref "U21") (pin "2") (pinfunction "-Ctrll_2") (pintype "passive"))
      (node (ref "U22") (pin "2") (pinfunction "-Ctrll_2") (pintype "passive"))
      (node (ref "U23") (pin "2") (pinfunction "-Ctrll_2") (pintype "passive"))
      (node (ref "U24") (pin "2") (pinfunction "-Ctrll_2") (pintype "passive"))
      (node (ref "U3") (pin "2") (pinfunction "-Ctrll_2") (pintype "passive"))
      (node (ref "U4") (pin "2") (pinfunction "-Ctrll_2") (pintype "passive"))
      (node (ref "U5") (pin "2") (pinfunction "-Ctrll_2") (pintype "passive"))
      (node (ref "U6") (pin "2") (pinfunction "-Ctrll_2") (pintype "passive"))
      (node (ref "U7") (pin "2") (pinfunction "-Ctrll_2") (pintype "passive"))
      (node (ref "U8") (pin "2") (pinfunction "-Ctrll_2") (pintype "passive"))
      (node (ref "U9") (pin "2") (pinfunction "-Ctrll_2") (pintype "passive"))
    )
  )
)
